# Sheet1.net
KiCad netlist of a schematic drawn in Altium Designer
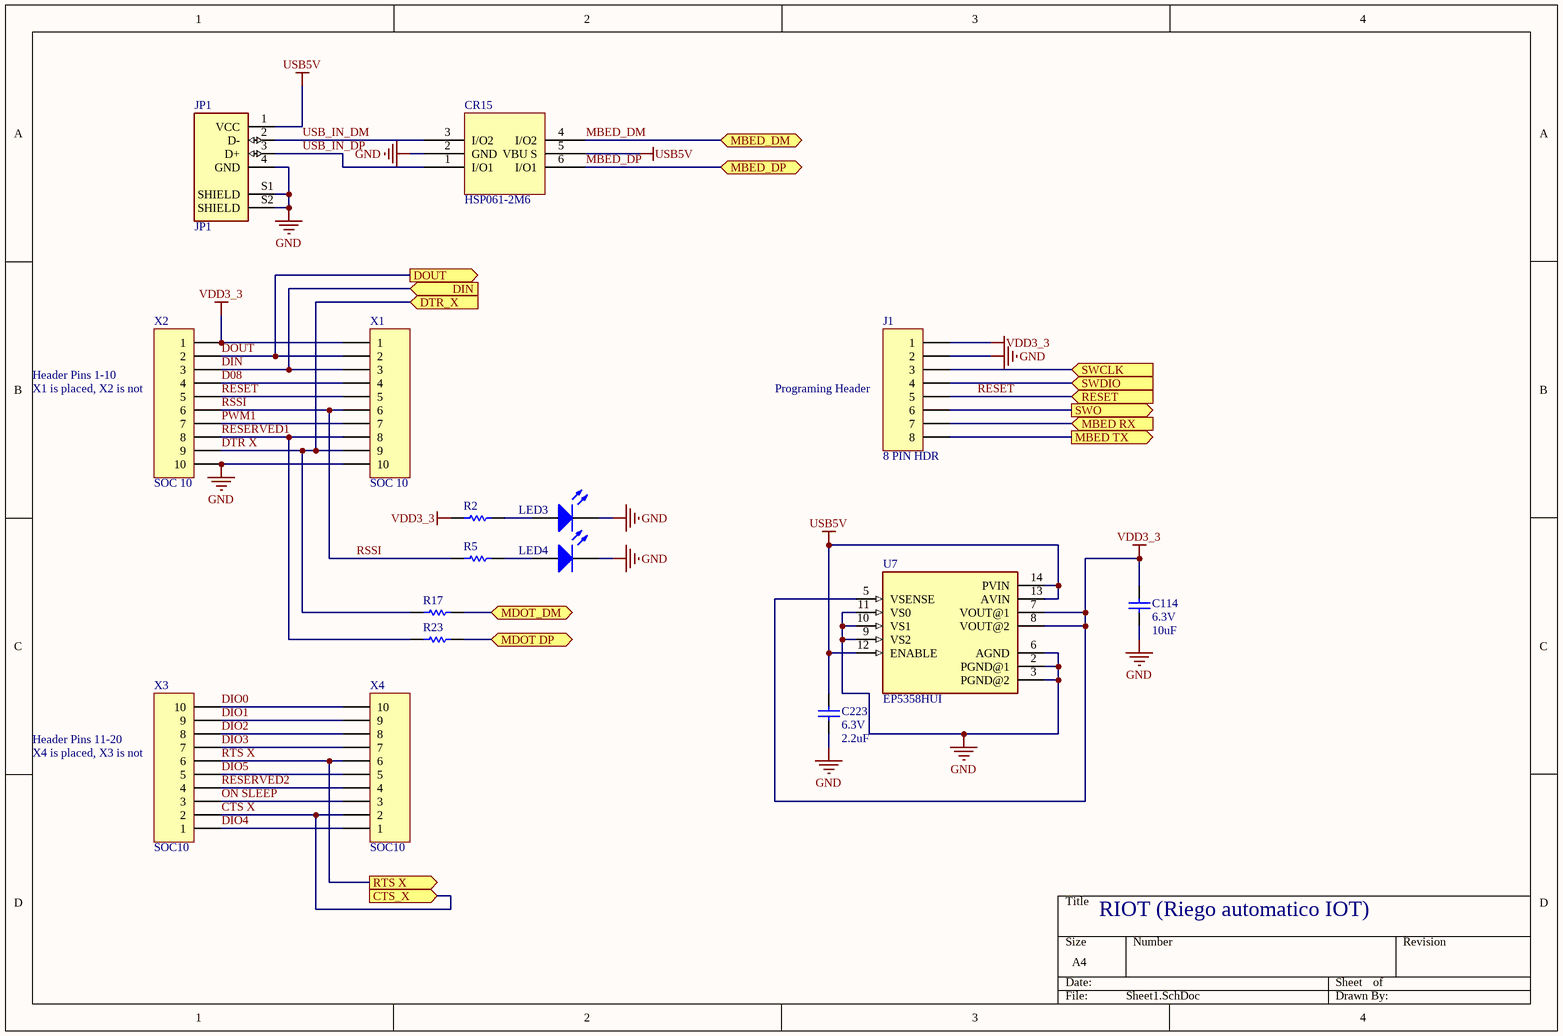
[diagram p0: Sheet1.SchDoc]

(export (version "E")
  (design (tool "Eeschema 10.0.6"))
  (components
    (comp (ref "C114")
      (value "6.3V")
      (footprint "CAPC1005X35N")
      (description "Capacitor")
      (fields (field (name "ALTIUM_VALUE") "10uF") (field (name "PUBLISHER") "Altium Limited"))
      (libsource (lib "Miscellaneous Devices") (part "Cap"))
    )
    (comp (ref "C223")
      (value "6.3V")
      (footprint "CAPC1005X35N")
      (description "Capacitor")
      (fields (field (name "ALTIUM_VALUE") "2.2uF") (field (name "PUBLISHER") "Altium Limited"))
      (libsource (lib "Miscellaneous Devices") (part "Cap"))
    )
    (comp (ref "CR15")
      (value "HSP061-2M6")
      (footprint "PSON40P120X130X55-6N")
      (libsource (lib "Components - 07.03.22 - 14.02") (part "HSP061-2M6"))
    )
    (comp (ref "J1")
      (value "8 PIN HDR")
      (footprint "HDR1X8")
      (description "Header, 8-Pin")
      (fields (field (name "PUBLISHER") "Altium Limited"))
      (libsource (lib "Miscellaneous Connectors") (part "Header 8"))
    )
    (comp (ref "JP1")
      (value "JP1")
      (footprint "GCT_USB1130-15-A_REVA")
      (fields (field (name "MP") "USB1130-15-A") (field (name "MF") "Global Connector Technology"))
      (libsource (lib "USB1130-15-A_REVA") (part "USB1130-15-A_REVA"))
    )
    (comp (ref "LED3")
      (value "LED0")
      (footprint "FP-SML-P11MTT86-MFG")
      (description "Typical INFRARED GaAs LED")
      (fields (field (name "PUBLISHER") "Altium Limited"))
      (libsource (lib "Miscellaneous Devices") (part "LED0"))
    )
    (comp (ref "LED4")
      (value "LED0")
      (footprint "FP-SML-P11MTT86-MFG")
      (description "Typical INFRARED GaAs LED")
      (fields (field (name "PUBLISHER") "Altium Limited"))
      (libsource (lib "Miscellaneous Devices") (part "LED0"))
    )
    (comp (ref "R2")
      (value "Res1")
      (footprint "RESC1005X35N")
      (description "Resistor")
      (fields (field (name "PUBLISHER") "Altium Limited"))
      (libsource (lib "Miscellaneous Devices") (part "Res1"))
    )
    (comp (ref "R5")
      (value "Res1")
      (footprint "RESC1005X35N")
      (description "Resistor")
      (fields (field (name "PUBLISHER") "Altium Limited"))
      (libsource (lib "Miscellaneous Devices") (part "Res1"))
    )
    (comp (ref "R17")
      (value "Res1")
      (footprint "RESC1005X35N")
      (description "Resistor")
      (fields (field (name "PUBLISHER") "Altium Limited"))
      (libsource (lib "Miscellaneous Devices") (part "Res1"))
    )
    (comp (ref "R23")
      (value "Res1")
      (footprint "RESC1005X35N")
      (description "Resistor")
      (fields (field (name "PUBLISHER") "Altium Limited"))
      (libsource (lib "Miscellaneous Devices") (part "Res1"))
    )
    (comp (ref "U7")
      (value "EP5358HUI")
      (footprint "QFN40P225X250X110-16N")
      (description "Non-Isolated PoL Module DC DC Converter 1 Output 1.8 ~ 3.3V 600mA 2.4V - 5.5V Input")
      (fields (field (name "DIGI-KEY_PART_NUMBER") "544-2870-1-ND") (field (name "MF") "Intel"))
      (libsource (lib "EP5358HUI") (part "EP5358HUI"))
    )
    (comp (ref "X1")
      (value "SOC 10")
      (footprint "HDR1X10")
      (description "Header, 10-Pin")
      (fields (field (name "PUBLISHER") "Altium Limited"))
      (libsource (lib "") (part "Header 10_3"))
    )
    (comp (ref "X2")
      (value "SOC 10")
      (footprint "HDR1X10")
      (description "Header, 10-Pin")
      (fields (field (name "PUBLISHER") "Altium Limited"))
      (libsource (lib "") (part "Header 10_1"))
    )
    (comp (ref "X3")
      (value "SOC10")
      (footprint "HDR1X10")
      (description "Header, 10-Pin")
      (fields (field (name "PUBLISHER") "Altium Limited"))
      (libsource (lib "Miscellaneous Connectors") (part "Header 10"))
    )
    (comp (ref "X4")
      (value "SOC10")
      (footprint "HDR1X10")
      (description "Header, 10-Pin")
      (fields (field (name "PUBLISHER") "Altium Limited"))
      (libsource (lib "") (part "Header 10_2"))
    )
  )
  (nets
    (net (code "1") (name "/CTS X") (class "Default")
      (node (ref "X3") (pin "2") (pinfunction "2_2") (pintype "passive"))
      (node (ref "X4") (pin "2") (pinfunction "2_2") (pintype "passive"))
    )
    (net (code "2") (name "/D08") (class "Default")
      (node (ref "X1") (pin "4") (pinfunction "4_4") (pintype "passive"))
      (node (ref "X2") (pin "4") (pinfunction "4_4") (pintype "passive"))
    )
    (net (code "3") (name "/DIN") (class "Default")
      (node (ref "X1") (pin "3") (pinfunction "3_3") (pintype "passive"))
      (node (ref "X2") (pin "3") (pinfunction "3_3") (pintype "passive"))
    )
    (net (code "4") (name "/DIO0") (class "Default")
      (node (ref "X3") (pin "10") (pinfunction "10_10") (pintype "passive"))
      (node (ref "X4") (pin "10") (pinfunction "10_10") (pintype "passive"))
    )
    (net (code "5") (name "/DIO1") (class "Default")
      (node (ref "X3") (pin "9") (pinfunction "9_9") (pintype "passive"))
      (node (ref "X4") (pin "9") (pinfunction "9_9") (pintype "passive"))
    )
    (net (code "6") (name "/DIO2") (class "Default")
      (node (ref "X3") (pin "8") (pinfunction "8_8") (pintype "passive"))
      (node (ref "X4") (pin "8") (pinfunction "8_8") (pintype "passive"))
    )
    (net (code "7") (name "/DIO3") (class "Default")
      (node (ref "X3") (pin "7") (pinfunction "7_7") (pintype "passive"))
      (node (ref "X4") (pin "7") (pinfunction "7_7") (pintype "passive"))
    )
    (net (code "8") (name "/DIO4") (class "Default")
      (node (ref "X3") (pin "1") (pinfunction "1_1") (pintype "passive"))
      (node (ref "X4") (pin "1") (pinfunction "1_1") (pintype "passive"))
    )
    (net (code "9") (name "/DIO5") (class "Default")
      (node (ref "X3") (pin "5") (pinfunction "5_5") (pintype "passive"))
      (node (ref "X4") (pin "5") (pinfunction "5_5") (pintype "passive"))
    )
    (net (code "10") (name "/DOUT") (class "Default")
      (node (ref "X1") (pin "2") (pinfunction "2_2") (pintype "passive"))
      (node (ref "X2") (pin "2") (pinfunction "2_2") (pintype "passive"))
    )
    (net (code "11") (name "/DTR X") (class "Default")
      (node (ref "R17") (pin "1") (pinfunction "1_1") (pintype "passive"))
      (node (ref "X1") (pin "9") (pinfunction "9_9") (pintype "passive"))
      (node (ref "X2") (pin "9") (pinfunction "9_9") (pintype "passive"))
    )
    (net (code "12") (name "/MBED RX") (class "Default")
      (node (ref "J1") (pin "7") (pinfunction "7_7") (pintype "passive"))
    )
    (net (code "13") (name "/MBED TX") (class "Default")
      (node (ref "J1") (pin "8") (pinfunction "8_8") (pintype "passive"))
    )
    (net (code "14") (name "/MBED_DM") (class "Default")
      (node (ref "CR15") (pin "4") (pinfunction "I/O2_4") (pintype "passive"))
    )
    (net (code "15") (name "/MBED_DP") (class "Default")
      (node (ref "CR15") (pin "6") (pinfunction "I/O1_6") (pintype "passive"))
    )
    (net (code "16") (name "/MDOT DP") (class "Default")
      (node (ref "R23") (pin "2") (pinfunction "2_2") (pintype "passive"))
    )
    (net (code "17") (name "/MDOT_DM") (class "Default")
      (node (ref "R17") (pin "2") (pinfunction "2_2") (pintype "passive"))
    )
    (net (code "18") (name "/ON SLEEP") (class "Default")
      (node (ref "X3") (pin "3") (pinfunction "3_3") (pintype "passive"))
      (node (ref "X4") (pin "3") (pinfunction "3_3") (pintype "passive"))
    )
    (net (code "19") (name "/PWM1") (class "Default")
      (node (ref "X1") (pin "7") (pinfunction "7_7") (pintype "passive"))
      (node (ref "X2") (pin "7") (pinfunction "7_7") (pintype "passive"))
    )
    (net (code "20") (name "/RESERVED1") (class "Default")
      (node (ref "R23") (pin "1") (pinfunction "1_1") (pintype "passive"))
      (node (ref "X1") (pin "8") (pinfunction "8_8") (pintype "passive"))
      (node (ref "X2") (pin "8") (pinfunction "8_8") (pintype "passive"))
    )
    (net (code "21") (name "/RESERVED2") (class "Default")
      (node (ref "X3") (pin "4") (pinfunction "4_4") (pintype "passive"))
      (node (ref "X4") (pin "4") (pinfunction "4_4") (pintype "passive"))
    )
    (net (code "22") (name "/RESET") (class "Default")
      (node (ref "J1") (pin "5") (pinfunction "5_5") (pintype "passive"))
      (node (ref "X1") (pin "5") (pinfunction "5_5") (pintype "passive"))
      (node (ref "X2") (pin "5") (pinfunction "5_5") (pintype "passive"))
    )
    (net (code "23") (name "/RSSI") (class "Default")
      (node (ref "R5") (pin "1") (pinfunction "1_1") (pintype "passive"))
      (node (ref "X1") (pin "6") (pinfunction "6_6") (pintype "passive"))
      (node (ref "X2") (pin "6") (pinfunction "6_6") (pintype "passive"))
    )
    (net (code "24") (name "/RTS X") (class "Default")
      (node (ref "X3") (pin "6") (pinfunction "6_6") (pintype "passive"))
      (node (ref "X4") (pin "6") (pinfunction "6_6") (pintype "passive"))
    )
    (net (code "25") (name "/SWCLK") (class "Default")
      (node (ref "J1") (pin "3") (pinfunction "3_3") (pintype "passive"))
    )
    (net (code "26") (name "/SWDIO") (class "Default")
      (node (ref "J1") (pin "4") (pinfunction "4_4") (pintype "passive"))
    )
    (net (code "27") (name "/SWO") (class "Default")
      (node (ref "J1") (pin "6") (pinfunction "6_6") (pintype "passive"))
    )
    (net (code "28") (name "/USB_IN_DM") (class "Default")
      (node (ref "CR15") (pin "3") (pinfunction "I/O2_3") (pintype "passive"))
      (node (ref "JP1") (pin "2") (pinfunction "D-_2") (pintype "bidirectional"))
    )
    (net (code "29") (name "/USB_IN_DP") (class "Default")
      (node (ref "CR15") (pin "1") (pinfunction "I/O1_1") (pintype "passive"))
      (node (ref "JP1") (pin "3") (pinfunction "D+_3") (pintype "bidirectional"))
    )
    (net (code "30") (name "GND") (class "Default")
      (node (ref "C114") (pin "1") (pinfunction "1_1") (pintype "passive"))
      (node (ref "C223") (pin "1") (pinfunction "1_1") (pintype "passive"))
      (node (ref "CR15") (pin "2") (pinfunction "GND_2") (pintype "passive"))
      (node (ref "J1") (pin "2") (pinfunction "2_2") (pintype "passive"))
      (node (ref "JP1") (pin "4") (pinfunction "GND_4") (pintype "power_in"))
      (node (ref "JP1") (pin "S1") (pinfunction "SHIELD_S1") (pintype "passive"))
      (node (ref "JP1") (pin "S2") (pinfunction "SHIELD_S2") (pintype "passive"))
      (node (ref "LED3") (pin "2") (pinfunction "K_2") (pintype "passive"))
      (node (ref "LED4") (pin "2") (pinfunction "K_2") (pintype "passive"))
      (node (ref "U7") (pin "10") (pinfunction "VS1_10") (pintype "input"))
      (node (ref "U7") (pin "11") (pinfunction "VS0_11") (pintype "input"))
      (node (ref "U7") (pin "2") (pinfunction "PGND@1_2") (pintype "power_in"))
      (node (ref "U7") (pin "3") (pinfunction "PGND@2_3") (pintype "power_in"))
      (node (ref "U7") (pin "6") (pinfunction "AGND_6") (pintype "power_in"))
      (node (ref "U7") (pin "9") (pinfunction "VS2_9") (pintype "input"))
      (node (ref "X1") (pin "10") (pinfunction "10_10") (pintype "passive"))
      (node (ref "X2") (pin "10") (pinfunction "10_10") (pintype "passive"))
    )
    (net (code "31") (name "Net-(LED3-A)") (class "Default")
      (node (ref "LED3") (pin "1") (pinfunction "A_1") (pintype "passive"))
      (node (ref "R2") (pin "2") (pinfunction "2_2") (pintype "passive"))
    )
    (net (code "32") (name "Net-(LED4-A)") (class "Default")
      (node (ref "LED4") (pin "1") (pinfunction "A_1") (pintype "passive"))
      (node (ref "R5") (pin "2") (pinfunction "2_2") (pintype "passive"))
    )
    (net (code "33") (name "USB5V") (class "Default")
      (node (ref "C223") (pin "2") (pinfunction "2_2") (pintype "passive"))
      (node (ref "CR15") (pin "5") (pinfunction "VBU_S_5") (pintype "passive"))
      (node (ref "JP1") (pin "1") (pinfunction "VCC_1") (pintype "power_in"))
      (node (ref "U7") (pin "12") (pinfunction "ENABLE_12") (pintype "input"))
      (node (ref "U7") (pin "13") (pinfunction "AVIN_13") (pintype "power_in"))
      (node (ref "U7") (pin "14") (pinfunction "PVIN_14") (pintype "power_in"))
    )
    (net (code "34") (name "VDD3_3") (class "Default")
      (node (ref "C114") (pin "2") (pinfunction "2_2") (pintype "passive"))
      (node (ref "J1") (pin "1") (pinfunction "1_1") (pintype "passive"))
      (node (ref "R2") (pin "1") (pinfunction "1_1") (pintype "passive"))
      (node (ref "U7") (pin "5") (pinfunction "VSENSE_5") (pintype "input"))
      (node (ref "U7") (pin "7") (pinfunction "VOUT@1_7") (pintype "passive"))
      (node (ref "U7") (pin "8") (pinfunction "VOUT@2_8") (pintype "passive"))
      (node (ref "X1") (pin "1") (pinfunction "1_1") (pintype "passive"))
      (node (ref "X2") (pin "1") (pinfunction "1_1") (pintype "passive"))
    )
  )
)
